# BT_Lamp_RC.net
KiCad netlist of a schematic drawn in Altium Designer
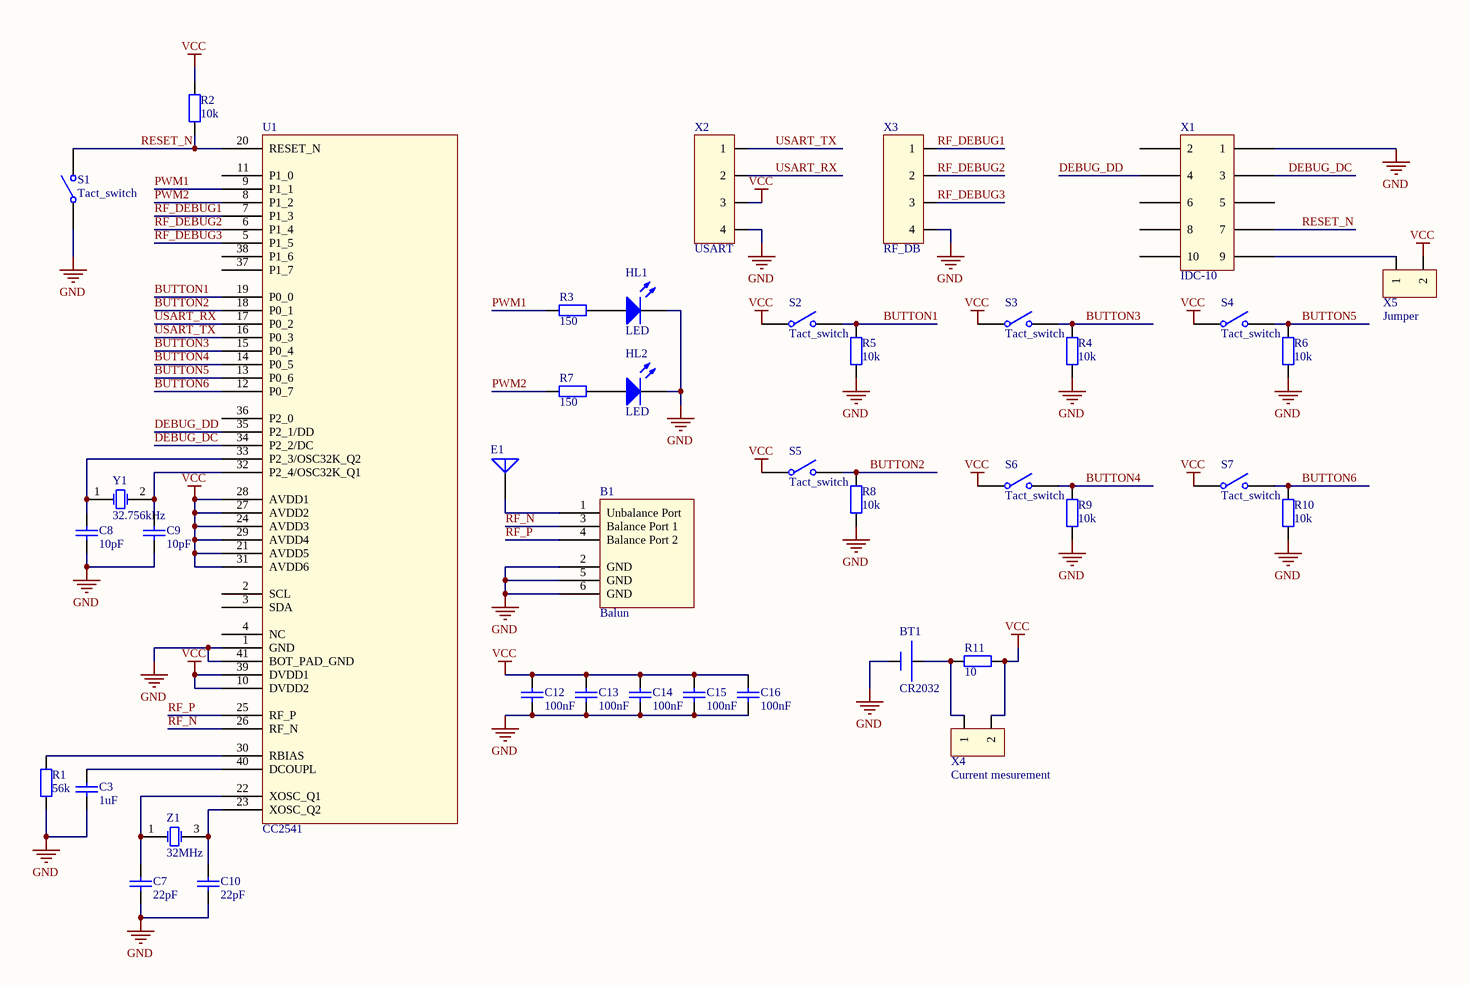
[diagram p0: BT_Lamp_RC.SchDoc]

(export (version "E")
  (design (tool "Eeschema 10.0.6"))
  (components
    (comp (ref "B1")
      (value "Balun")
      (footprint "A_H_pcb_lib:2.4 Balun 50Ohm LFB182G45BG2D280")
      (libsource (lib "A_H_sch_lib") (part "2.4 Balun 50Ohm LFB182G45BG2D280"))
    )
    (comp (ref "BT1")
      (value "CR2032")
      (footprint "BH-642(CR2032)")
      (libsource (lib "A_H_sch_lib") (part "CR2032_Holder_BH-642"))
    )
    (comp (ref "C3")
      (value "1uF")
      (footprint "A_H_pcb_lib:C0603")
      (libsource (lib "A_H_sch_lib") (part "Condensator"))
    )
    (comp (ref "C7")
      (value "22pF")
      (footprint "A_H_pcb_lib:C0603")
      (libsource (lib "A_H_sch_lib") (part "Condensator"))
    )
    (comp (ref "C8")
      (value "10pF")
      (footprint "A_H_pcb_lib:C0603")
      (libsource (lib "A_H_sch_lib") (part "Condensator"))
    )
    (comp (ref "C9")
      (value "10pF")
      (footprint "A_H_pcb_lib:C0603")
      (libsource (lib "A_H_sch_lib") (part "Condensator"))
    )
    (comp (ref "C10")
      (value "22pF")
      (footprint "A_H_pcb_lib:C0603")
      (libsource (lib "A_H_sch_lib") (part "Condensator"))
    )
    (comp (ref "C12")
      (value "100nF")
      (footprint "A_H_pcb_lib:C0603")
      (libsource (lib "A_H_sch_lib") (part "Condensator"))
    )
    (comp (ref "C13")
      (value "100nF")
      (footprint "A_H_pcb_lib:C0603")
      (libsource (lib "A_H_sch_lib") (part "Condensator"))
    )
    (comp (ref "C14")
      (value "100nF")
      (footprint "A_H_pcb_lib:C0603")
      (libsource (lib "A_H_sch_lib") (part "Condensator"))
    )
    (comp (ref "C15")
      (value "100nF")
      (footprint "A_H_pcb_lib:C0603")
      (libsource (lib "A_H_sch_lib") (part "Condensator"))
    )
    (comp (ref "C16")
      (value "100nF")
      (footprint "A_H_pcb_lib:C0603")
      (libsource (lib "A_H_sch_lib") (part "Condensator"))
    )
    (comp (ref "E1")
      (value "Antenna")
      (footprint "A_H_pcb_lib:2.4 INF Antenna")
      (libsource (lib "A_H_sch_lib") (part "Antenna"))
    )
    (comp (ref "HL1")
      (value "LED")
      (footprint "A_H_pcb_lib:LED_0805")
      (libsource (lib "A_H_sch_lib") (part "LED"))
    )
    (comp (ref "HL2")
      (value "LED")
      (footprint "A_H_pcb_lib:LED_0805")
      (libsource (lib "A_H_sch_lib") (part "LED"))
    )
    (comp (ref "R1")
      (value "56k")
      (footprint "A_H_pcb_lib:R0603")
      (libsource (lib "A_H_sch_lib") (part "Resistor"))
    )
    (comp (ref "R2")
      (value "10k")
      (footprint "A_H_pcb_lib:R0603")
      (libsource (lib "A_H_sch_lib") (part "Resistor"))
    )
    (comp (ref "R3") (value "150") (footprint "A_H_pcb_lib:R0603") (libsource (lib "") (part "Resistor_2")))
    (comp (ref "R4")
      (value "10k")
      (footprint "A_H_pcb_lib:R0603")
      (libsource (lib "A_H_sch_lib") (part "Resistor"))
    )
    (comp (ref "R5")
      (value "10k")
      (footprint "A_H_pcb_lib:R0603")
      (libsource (lib "A_H_sch_lib") (part "Resistor"))
    )
    (comp (ref "R6")
      (value "10k")
      (footprint "A_H_pcb_lib:R0603")
      (libsource (lib "A_H_sch_lib") (part "Resistor"))
    )
    (comp (ref "R7") (value "150") (footprint "A_H_pcb_lib:R0603") (libsource (lib "") (part "Resistor_2")))
    (comp (ref "R8")
      (value "10k")
      (footprint "A_H_pcb_lib:R0603")
      (libsource (lib "A_H_sch_lib") (part "Resistor"))
    )
    (comp (ref "R9")
      (value "10k")
      (footprint "A_H_pcb_lib:R0603")
      (libsource (lib "A_H_sch_lib") (part "Resistor"))
    )
    (comp (ref "R10")
      (value "10k")
      (footprint "A_H_pcb_lib:R0603")
      (libsource (lib "A_H_sch_lib") (part "Resistor"))
    )
    (comp (ref "R11") (value "10") (footprint "A_H_pcb_lib:R0603") (libsource (lib "") (part "Resistor_1")))
    (comp (ref "S1")
      (value "Tact_switch")
      (footprint "Tact_switch_smd")
      (libsource (lib "A_H_sch_lib") (part "Tact_switch"))
    )
    (comp (ref "S2")
      (value "Tact_switch")
      (footprint "Tact_switch_smd")
      (libsource (lib "A_H_sch_lib") (part "Tact_switch"))
    )
    (comp (ref "S3")
      (value "Tact_switch")
      (footprint "Tact_switch_smd")
      (libsource (lib "A_H_sch_lib") (part "Tact_switch"))
    )
    (comp (ref "S4")
      (value "Tact_switch")
      (footprint "Tact_switch_smd")
      (libsource (lib "A_H_sch_lib") (part "Tact_switch"))
    )
    (comp (ref "S5")
      (value "Tact_switch")
      (footprint "Tact_switch_smd")
      (libsource (lib "A_H_sch_lib") (part "Tact_switch"))
    )
    (comp (ref "S6")
      (value "Tact_switch")
      (footprint "Tact_switch_smd")
      (libsource (lib "A_H_sch_lib") (part "Tact_switch"))
    )
    (comp (ref "S7")
      (value "Tact_switch")
      (footprint "Tact_switch_smd")
      (libsource (lib "A_H_sch_lib") (part "Tact_switch"))
    )
    (comp (ref "U1")
      (value "CC2541")
      (footprint "A_H_pcb_lib:QFN40 6x6 0.5pitch")
      (libsource (lib "A_H_sch_lib") (part "CC2541"))
    )
    (comp (ref "X1")
      (value "IDC-10")
      (footprint "A_H_pcb_lib:IDC-10")
      (libsource (lib "A_H_sch_lib") (part "IDC-10"))
    )
    (comp (ref "X2")
      (value "USART")
      (footprint "Pins 4x2.54")
      (libsource (lib "A_H_sch_lib") (part "Pins 4x2.54"))
    )
    (comp (ref "X3")
      (value "RF_DB")
      (footprint "Pins 4x2.54")
      (libsource (lib "A_H_sch_lib") (part "Pins 4x2.54"))
    )
    (comp (ref "X4")
      (value "Current mesurement")
      (footprint "Pins 2x2.54")
      (libsource (lib "A_H_sch_lib") (part "Pins 2x2.54"))
    )
    (comp (ref "X5")
      (value "Jumper")
      (footprint "Pins 2x2.54")
      (libsource (lib "A_H_sch_lib") (part "Pins 2x2.54"))
    )
    (comp (ref "Y1")
      (value "32.756kHz")
      (footprint "Geyer KX - 327S 32.768kHz")
      (libsource (lib "A_H_sch_lib") (part "Crystal Oscillator"))
    )
    (comp (ref "Z1")
      (value "32MHz")
      (footprint "kx 13 12MHz")
      (libsource (lib "A_H_sch_lib") (part "KX 13 Geyer"))
    )
  )
  (nets
    (net (code "1") (name "/BUTTON1") (class "Default")
      (node (ref "R5") (pin "2") (pinfunction "2_2") (pintype "passive"))
      (node (ref "S2") (pin "2") (pinfunction "NO_2") (pintype "passive"))
      (node (ref "U1") (pin "19") (pinfunction "P0_0_19") (pintype "passive"))
    )
    (net (code "2") (name "/BUTTON2") (class "Default")
      (node (ref "R8") (pin "2") (pinfunction "2_2") (pintype "passive"))
      (node (ref "S5") (pin "2") (pinfunction "NO_2") (pintype "passive"))
      (node (ref "U1") (pin "18") (pinfunction "P0_1_18") (pintype "passive"))
    )
    (net (code "3") (name "/BUTTON3") (class "Default")
      (node (ref "R4") (pin "2") (pinfunction "2_2") (pintype "passive"))
      (node (ref "S3") (pin "2") (pinfunction "NO_2") (pintype "passive"))
      (node (ref "U1") (pin "15") (pinfunction "P0_4_15") (pintype "passive"))
    )
    (net (code "4") (name "/BUTTON4") (class "Default")
      (node (ref "R9") (pin "2") (pinfunction "2_2") (pintype "passive"))
      (node (ref "S6") (pin "2") (pinfunction "NO_2") (pintype "passive"))
      (node (ref "U1") (pin "14") (pinfunction "P0_5_14") (pintype "passive"))
    )
    (net (code "5") (name "/BUTTON5") (class "Default")
      (node (ref "R6") (pin "2") (pinfunction "2_2") (pintype "passive"))
      (node (ref "S4") (pin "2") (pinfunction "NO_2") (pintype "passive"))
      (node (ref "U1") (pin "13") (pinfunction "P0_6_13") (pintype "passive"))
    )
    (net (code "6") (name "/BUTTON6") (class "Default")
      (node (ref "R10") (pin "2") (pinfunction "2_2") (pintype "passive"))
      (node (ref "S7") (pin "2") (pinfunction "NO_2") (pintype "passive"))
      (node (ref "U1") (pin "12") (pinfunction "P0_7_12") (pintype "passive"))
    )
    (net (code "7") (name "/DEBUG_DC") (class "Default")
      (node (ref "U1") (pin "34") (pinfunction "P2_2/DC_34") (pintype "passive"))
      (node (ref "X1") (pin "3") (pinfunction "3_3") (pintype "passive"))
    )
    (net (code "8") (name "/DEBUG_DD") (class "Default")
      (node (ref "U1") (pin "35") (pinfunction "P2_1/DD_35") (pintype "passive"))
      (node (ref "X1") (pin "4") (pinfunction "4_4") (pintype "passive"))
    )
    (net (code "9") (name "/PWM1") (class "Default")
      (node (ref "R3") (pin "2") (pinfunction "2_2") (pintype "passive"))
      (node (ref "U1") (pin "9") (pinfunction "P1_1_9") (pintype "passive"))
    )
    (net (code "10") (name "/PWM2") (class "Default")
      (node (ref "R7") (pin "2") (pinfunction "2_2") (pintype "passive"))
      (node (ref "U1") (pin "8") (pinfunction "P1_2_8") (pintype "passive"))
    )
    (net (code "11") (name "/RESET_N") (class "Default")
      (node (ref "R2") (pin "1") (pinfunction "1_1") (pintype "passive"))
      (node (ref "S1") (pin "2") (pinfunction "NO_2") (pintype "passive"))
      (node (ref "U1") (pin "20") (pinfunction "RESET_N_20") (pintype "passive"))
      (node (ref "X1") (pin "7") (pinfunction "7_7") (pintype "passive"))
    )
    (net (code "12") (name "/RF_DEBUG1") (class "Default")
      (node (ref "U1") (pin "7") (pinfunction "P1_3_7") (pintype "passive"))
      (node (ref "X3") (pin "1") (pinfunction "1_1") (pintype "passive"))
    )
    (net (code "13") (name "/RF_DEBUG2") (class "Default")
      (node (ref "U1") (pin "6") (pinfunction "P1_4_6") (pintype "passive"))
      (node (ref "X3") (pin "2") (pinfunction "2_2") (pintype "passive"))
    )
    (net (code "14") (name "/RF_DEBUG3") (class "Default")
      (node (ref "U1") (pin "5") (pinfunction "P1_5_5") (pintype "passive"))
      (node (ref "X3") (pin "3") (pinfunction "3_3") (pintype "passive"))
    )
    (net (code "15") (name "/RF_N") (class "Default")
      (node (ref "B1") (pin "3") (pinfunction "Balance_Port_1_3") (pintype "passive"))
      (node (ref "U1") (pin "26") (pinfunction "RF_N_26") (pintype "passive"))
    )
    (net (code "16") (name "/RF_P") (class "Default")
      (node (ref "B1") (pin "4") (pinfunction "Balance_Port_2_4") (pintype "passive"))
      (node (ref "U1") (pin "25") (pinfunction "RF_P_25") (pintype "passive"))
    )
    (net (code "17") (name "/USART_RX") (class "Default")
      (node (ref "U1") (pin "17") (pinfunction "P0_2_17") (pintype "passive"))
      (node (ref "X2") (pin "2") (pinfunction "2_2") (pintype "passive"))
    )
    (net (code "18") (name "/USART_TX") (class "Default")
      (node (ref "U1") (pin "16") (pinfunction "P0_3_16") (pintype "passive"))
      (node (ref "X2") (pin "1") (pinfunction "1_1") (pintype "passive"))
    )
    (net (code "19") (name "GND") (class "Default")
      (node (ref "B1") (pin "2") (pinfunction "GND_2") (pintype "passive"))
      (node (ref "B1") (pin "5") (pinfunction "GND_5") (pintype "passive"))
      (node (ref "B1") (pin "6") (pinfunction "GND_6") (pintype "passive"))
      (node (ref "BT1") (pin "1") (pinfunction "1_1") (pintype "passive"))
      (node (ref "C10") (pin "1") (pinfunction "1_1") (pintype "passive"))
      (node (ref "C12") (pin "2") (pinfunction "2_2") (pintype "passive"))
      (node (ref "C13") (pin "2") (pinfunction "2_2") (pintype "passive"))
      (node (ref "C14") (pin "2") (pinfunction "2_2") (pintype "passive"))
      (node (ref "C15") (pin "2") (pinfunction "2_2") (pintype "passive"))
      (node (ref "C16") (pin "2") (pinfunction "2_2") (pintype "passive"))
      (node (ref "C3") (pin "1") (pinfunction "1_1") (pintype "passive"))
      (node (ref "C7") (pin "1") (pinfunction "1_1") (pintype "passive"))
      (node (ref "C8") (pin "1") (pinfunction "1_1") (pintype "passive"))
      (node (ref "C9") (pin "1") (pinfunction "1_1") (pintype "passive"))
      (node (ref "HL1") (pin "2") (pinfunction "K_2") (pintype "passive"))
      (node (ref "HL2") (pin "2") (pinfunction "K_2") (pintype "passive"))
      (node (ref "R1") (pin "1") (pinfunction "1_1") (pintype "passive"))
      (node (ref "R10") (pin "1") (pinfunction "1_1") (pintype "passive"))
      (node (ref "R4") (pin "1") (pinfunction "1_1") (pintype "passive"))
      (node (ref "R5") (pin "1") (pinfunction "1_1") (pintype "passive"))
      (node (ref "R6") (pin "1") (pinfunction "1_1") (pintype "passive"))
      (node (ref "R8") (pin "1") (pinfunction "1_1") (pintype "passive"))
      (node (ref "R9") (pin "1") (pinfunction "1_1") (pintype "passive"))
      (node (ref "S1") (pin "1") (pinfunction "COMMON_1") (pintype "passive"))
      (node (ref "U1") (pin "1") (pinfunction "GND_1") (pintype "passive"))
      (node (ref "U1") (pin "41") (pinfunction "BOT_PAD_GND_41") (pintype "passive"))
      (node (ref "X1") (pin "1") (pinfunction "1_1") (pintype "passive"))
      (node (ref "X2") (pin "4") (pinfunction "4_4") (pintype "passive"))
      (node (ref "X3") (pin "4") (pinfunction "4_4") (pintype "passive"))
    )
    (net (code "20") (name "Net-(B1-Unbalance_Port)") (class "Default")
      (node (ref "B1") (pin "1") (pinfunction "Unbalance_Port_1") (pintype "passive"))
      (node (ref "E1") (pin "1") (pinfunction "A_1") (pintype "passive"))
    )
    (net (code "21") (name "Net-(BT1-Pad2)") (class "Default")
      (node (ref "BT1") (pin "2") (pinfunction "2_2") (pintype "passive"))
      (node (ref "R11") (pin "1") (pinfunction "1_1") (pintype "passive"))
      (node (ref "X4") (pin "1") (pinfunction "1_1") (pintype "passive"))
    )
    (net (code "22") (name "Net-(HL1-A)") (class "Default")
      (node (ref "HL1") (pin "1") (pinfunction "A_1") (pintype "passive"))
      (node (ref "R3") (pin "1") (pinfunction "1_1") (pintype "passive"))
    )
    (net (code "23") (name "Net-(HL2-A)") (class "Default")
      (node (ref "HL2") (pin "1") (pinfunction "A_1") (pintype "passive"))
      (node (ref "R7") (pin "1") (pinfunction "1_1") (pintype "passive"))
    )
    (net (code "24") (name "Net-(U1-DCOUPL)") (class "Default")
      (node (ref "C3") (pin "2") (pinfunction "2_2") (pintype "passive"))
      (node (ref "U1") (pin "40") (pinfunction "DCOUPL_40") (pintype "passive"))
    )
    (net (code "25") (name "Net-(U1-P2_3{slash}OSC32K_Q2)") (class "Default")
      (node (ref "C8") (pin "2") (pinfunction "2_2") (pintype "passive"))
      (node (ref "U1") (pin "33") (pinfunction "P2_3/OSC32K_Q2_33") (pintype "passive"))
      (node (ref "Y1") (pin "1") (pinfunction "OSC1_1") (pintype "passive"))
    )
    (net (code "26") (name "Net-(U1-P2_4{slash}OSC32K_Q1)") (class "Default")
      (node (ref "C9") (pin "2") (pinfunction "2_2") (pintype "passive"))
      (node (ref "U1") (pin "32") (pinfunction "P2_4/OSC32K_Q1_32") (pintype "passive"))
      (node (ref "Y1") (pin "2") (pinfunction "OSC2_2") (pintype "passive"))
    )
    (net (code "27") (name "Net-(U1-RBIAS)") (class "Default")
      (node (ref "R1") (pin "2") (pinfunction "2_2") (pintype "passive"))
      (node (ref "U1") (pin "30") (pinfunction "RBIAS_30") (pintype "passive"))
    )
    (net (code "28") (name "Net-(U1-XOSC_Q1)") (class "Default")
      (node (ref "C7") (pin "2") (pinfunction "2_2") (pintype "passive"))
      (node (ref "U1") (pin "22") (pinfunction "XOSC_Q1_22") (pintype "passive"))
      (node (ref "Z1") (pin "1") (pinfunction "OSC1_1") (pintype "passive"))
    )
    (net (code "29") (name "Net-(U1-XOSC_Q2)") (class "Default")
      (node (ref "C10") (pin "2") (pinfunction "2_2") (pintype "passive"))
      (node (ref "U1") (pin "23") (pinfunction "XOSC_Q2_23") (pintype "passive"))
      (node (ref "Z1") (pin "3") (pinfunction "OSC2_3") (pintype "passive"))
    )
    (net (code "30") (name "Net-(X1-Pad9)") (class "Default")
      (node (ref "X1") (pin "9") (pinfunction "9_9") (pintype "passive"))
      (node (ref "X5") (pin "1") (pinfunction "1_1") (pintype "passive"))
    )
    (net (code "31") (name "VCC") (class "Default")
      (node (ref "C12") (pin "1") (pinfunction "1_1") (pintype "passive"))
      (node (ref "C13") (pin "1") (pinfunction "1_1") (pintype "passive"))
      (node (ref "C14") (pin "1") (pinfunction "1_1") (pintype "passive"))
      (node (ref "C15") (pin "1") (pinfunction "1_1") (pintype "passive"))
      (node (ref "C16") (pin "1") (pinfunction "1_1") (pintype "passive"))
      (node (ref "R11") (pin "2") (pinfunction "2_2") (pintype "passive"))
      (node (ref "R2") (pin "2") (pinfunction "2_2") (pintype "passive"))
      (node (ref "S2") (pin "1") (pinfunction "COMMON_1") (pintype "passive"))
      (node (ref "S3") (pin "1") (pinfunction "COMMON_1") (pintype "passive"))
      (node (ref "S4") (pin "1") (pinfunction "COMMON_1") (pintype "passive"))
      (node (ref "S5") (pin "1") (pinfunction "COMMON_1") (pintype "passive"))
      (node (ref "S6") (pin "1") (pinfunction "COMMON_1") (pintype "passive"))
      (node (ref "S7") (pin "1") (pinfunction "COMMON_1") (pintype "passive"))
      (node (ref "U1") (pin "10") (pinfunction "DVDD2_10") (pintype "passive"))
      (node (ref "U1") (pin "21") (pinfunction "AVDD5_21") (pintype "passive"))
      (node (ref "U1") (pin "24") (pinfunction "AVDD3_24") (pintype "passive"))
      (node (ref "U1") (pin "27") (pinfunction "AVDD2_27") (pintype "passive"))
      (node (ref "U1") (pin "28") (pinfunction "AVDD1_28") (pintype "passive"))
      (node (ref "U1") (pin "29") (pinfunction "AVDD4_29") (pintype "passive"))
      (node (ref "U1") (pin "31") (pinfunction "AVDD6_31") (pintype "passive"))
      (node (ref "U1") (pin "39") (pinfunction "DVDD1_39") (pintype "passive"))
      (node (ref "X2") (pin "3") (pinfunction "3_3") (pintype "passive"))
      (node (ref "X4") (pin "2") (pinfunction "2_2") (pintype "passive"))
      (node (ref "X5") (pin "2") (pinfunction "2_2") (pintype "passive"))
    )
    (net (code "32") (name "unconnected-(U1-NC-Pad4)") (class "Default")
      (node (ref "U1") (pin "4") (pinfunction "NC_4") (pintype "passive"))
    )
    (net (code "33") (name "unconnected-(U1-P1_0-Pad11)") (class "Default")
      (node (ref "U1") (pin "11") (pinfunction "P1_0_11") (pintype "passive"))
    )
    (net (code "34") (name "unconnected-(U1-P1_6-Pad38)") (class "Default")
      (node (ref "U1") (pin "38") (pinfunction "P1_6_38") (pintype "passive"))
    )
    (net (code "35") (name "unconnected-(U1-P1_7-Pad37)") (class "Default")
      (node (ref "U1") (pin "37") (pinfunction "P1_7_37") (pintype "passive"))
    )
    (net (code "36") (name "unconnected-(U1-P2_0-Pad36)") (class "Default")
      (node (ref "U1") (pin "36") (pinfunction "P2_0_36") (pintype "passive"))
    )
    (net (code "37") (name "unconnected-(U1-SCL-Pad2)") (class "Default")
      (node (ref "U1") (pin "2") (pinfunction "SCL_2") (pintype "passive"))
    )
    (net (code "38") (name "unconnected-(U1-SDA-Pad3)") (class "Default")
      (node (ref "U1") (pin "3") (pinfunction "SDA_3") (pintype "passive"))
    )
    (net (code "39") (name "unconnected-(X1-Pad2)") (class "Default")
      (node (ref "X1") (pin "2") (pinfunction "2_2") (pintype "passive"))
    )
    (net (code "40") (name "unconnected-(X1-Pad5)") (class "Default")
      (node (ref "X1") (pin "5") (pinfunction "5_5") (pintype "passive"))
    )
    (net (code "41") (name "unconnected-(X1-Pad6)") (class "Default")
      (node (ref "X1") (pin "6") (pinfunction "6_6") (pintype "passive"))
    )
    (net (code "42") (name "unconnected-(X1-Pad8)") (class "Default")
      (node (ref "X1") (pin "8") (pinfunction "8_8") (pintype "passive"))
    )
    (net (code "43") (name "unconnected-(X1-Pad10)") (class "Default")
      (node (ref "X1") (pin "10") (pinfunction "10_10") (pintype "passive"))
    )
  )
)
